# rpi-zero-psu.net
KiCad netlist of a schematic drawn in EAGLE
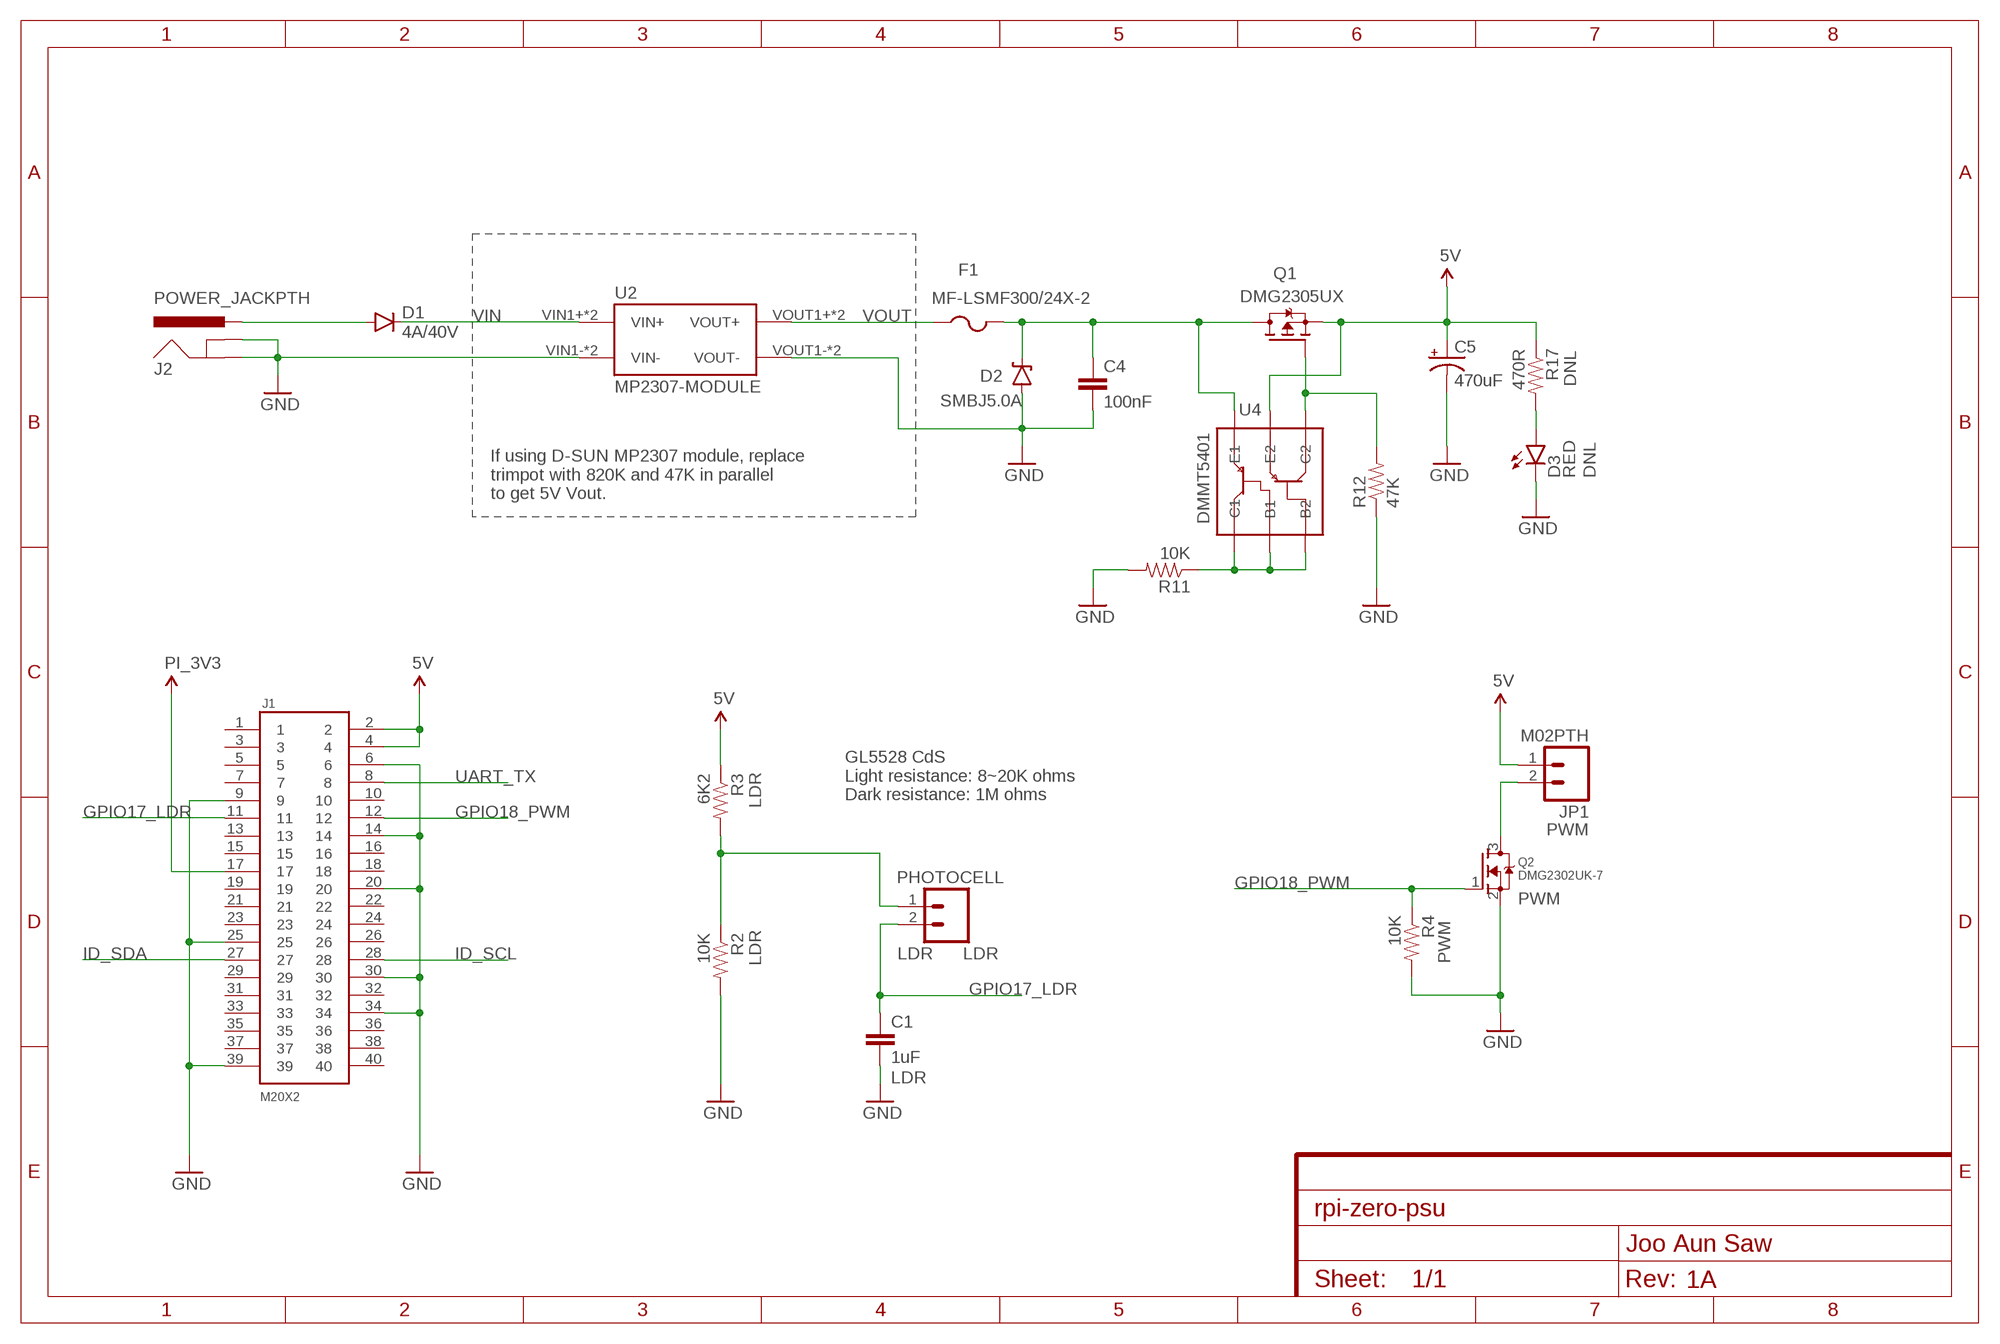
[diagram p0: schematic, sheet 1]

(export (version "E")
  (design (tool "Eeschema 10.0.6"))
  (components
    (comp (ref "C1")
      (value "1uF")
      (footprint "eagle-import:0805")
      (fields (field (name "PARTNO") "CC0805KKX7R8BB105"))
      (libsource (lib "eagle-import") (part "CAP0805"))
    )
    (comp (ref "C4")
      (value "100nF")
      (footprint "eagle-import:0805")
      (fields (field (name "PARTNO") "08055C104KAT2A"))
      (libsource (lib "eagle-import") (part "CAP0805"))
    )
    (comp (ref "C5")
      (value "470uF")
      (footprint "eagle-import:PANASONIC_F")
      (fields (field (name "ALT_PARTNO") "EEE-1CA471UP") (field (name "PARTNO") "875115150005"))
      (libsource (lib "eagle-import") (part "CAP_POLF"))
    )
    (comp (ref "D1")
      (value "4A/40V")
      (footprint "eagle-import:SMC")
      (fields (field (name "PARTNO") "MBRS340T3G"))
      (libsource (lib "eagle-import") (part "DIODEES3J"))
    )
    (comp (ref "D2")
      (value "SMBJ5.0A")
      (footprint "eagle-import:SMB-DIODE")
      (libsource (lib "eagle-import") (part "DIODE-ZENERSMB"))
    )
    (comp (ref "D3")
      (value "RED")
      (footprint "eagle-import:LED-1206")
      (fields (field (name "PARTNO") "LTST-C150CKT"))
      (libsource (lib "eagle-import") (part "LED-RED1206"))
    )
    (comp (ref "F1")
      (value "MF-LSMF300/24X-2")
      (footprint "eagle-import:2920")
      (libsource (lib "eagle-import") (part "PTCFUSE-2920"))
    )
    (comp (ref "J1")
      (value "M20X2")
      (footprint "eagle-import:2X20")
      (fields (field (name "PARTNO") "PPPC202LFBN-RC"))
      (libsource (lib "eagle-import") (part "M20X2"))
    )
    (comp (ref "J2")
      (value "POWER_JACKPTH")
      (footprint "eagle-import:POWER_JACK_PTH")
      (fields (field (name "PARTNO") "PJ-002A"))
      (libsource (lib "eagle-import") (part "POWER_JACKPTH"))
    )
    (comp (ref "JP1")
      (value "M02PTH")
      (footprint "eagle-import:1X02")
      (fields (field (name "PARTNO") "826936-2"))
      (libsource (lib "eagle-import") (part "M02PTH"))
    )
    (comp (ref "LDR")
      (value "PHOTOCELL")
      (footprint "eagle-import:1X02_NO_SILK")
      (libsource (lib "eagle-import") (part "M021X02_NO_SILK"))
    )
    (comp (ref "Q1")
      (value "DMG2305UX")
      (footprint "eagle-import:SOT-23")
      (fields (field (name "PARTNO") "DMG2305UX-7"))
      (libsource (lib "eagle-import") (part "MOSFET-P"))
    )
    (comp (ref "Q2")
      (value "DMG2302UK-7")
      (footprint "eagle-import:SOT23")
      (libsource (lib "eagle-import") (part "MOSFET-NREFLOW"))
    )
    (comp (ref "R2")
      (value "10K")
      (footprint "eagle-import:0805")
      (fields (field (name "PARTNO") "RC0805JR-0710KL"))
      (libsource (lib "eagle-import") (part "RESISTOR0805-RES"))
    )
    (comp (ref "R3")
      (value "6K2")
      (footprint "eagle-import:0805")
      (fields (field (name "PARTNO") "RC0805JR-076K2L"))
      (libsource (lib "eagle-import") (part "RESISTOR0805-RES"))
    )
    (comp (ref "R4")
      (value "10K")
      (footprint "eagle-import:0805")
      (fields (field (name "PARTNO") "RC0805JR-0710KL"))
      (libsource (lib "eagle-import") (part "RESISTOR0805-RES"))
    )
    (comp (ref "R11")
      (value "10K")
      (footprint "eagle-import:0805")
      (fields (field (name "PARTNO") "RC0805JR-0710KL"))
      (libsource (lib "eagle-import") (part "RESISTOR0805-RES"))
    )
    (comp (ref "R12")
      (value "47K")
      (footprint "eagle-import:0805")
      (fields (field (name "PARTNO") "RC0805FR-0747KL"))
      (libsource (lib "eagle-import") (part "RESISTOR0805-RES"))
    )
    (comp (ref "R17")
      (value "470R")
      (footprint "eagle-import:0805")
      (fields (field (name "PARTNO") "RC0805JR-07470RL"))
      (libsource (lib "eagle-import") (part "RESISTOR0805-RES"))
    )
    (comp (ref "U2")
      (value "MP2307-MODULE")
      (footprint "eagle-import:MP1584EN-MODULE")
      (fields (field (name "ALT_PARTNO") "IM130731001") (field (name "PARTNO") "106990005"))
      (libsource (lib "eagle-import") (part "DC-DC-MODULEMP2307-MODULE"))
    )
    (comp (ref "U4")
      (value "DMMT5401")
      (footprint "eagle-import:SOT23-6")
      (fields (field (name "PARTNO") "DMMT5401-7-F"))
      (libsource (lib "eagle-import") (part "DMMT5401SOT"))
    )
  )
  (nets
    (net (code "1") (name "/GPIO17_LDR") (class "Default")
      (node (ref "C1") (pin "1") (pinfunction "1_1") (pintype "passive"))
      (node (ref "J1") (pin "11") (pinfunction "11_11") (pintype "bidirectional"))
      (node (ref "LDR") (pin "2") (pinfunction "2_2") (pintype "passive"))
    )
    (net (code "2") (name "/GPIO18_PWM") (class "Default")
      (node (ref "J1") (pin "12") (pinfunction "12_12") (pintype "bidirectional"))
      (node (ref "Q2") (pin "1") (pinfunction "G_1") (pintype "bidirectional"))
      (node (ref "R4") (pin "1") (pinfunction "1_1") (pintype "passive"))
    )
    (net (code "3") (name "/ID_SCL") (class "Default")
      (node (ref "J1") (pin "28") (pinfunction "28_28") (pintype "bidirectional"))
    )
    (net (code "4") (name "/ID_SDA") (class "Default")
      (node (ref "J1") (pin "27") (pinfunction "27_27") (pintype "bidirectional"))
    )
    (net (code "5") (name "/UART_TX") (class "Default")
      (node (ref "J1") (pin "8") (pinfunction "8_8") (pintype "bidirectional"))
    )
    (net (code "6") (name "/VIN") (class "Default")
      (node (ref "D1") (pin "C") (pinfunction "C_C") (pintype "passive"))
      (node (ref "U2") (pin "VIN1+") (pinfunction "VIN+_VIN1+") (pintype "bidirectional"))
      (node (ref "U2") (pin "VIN2+") (pinfunction "VIN+_VIN2+") (pintype "bidirectional"))
    )
    (net (code "7") (name "/VOUT") (class "Default")
      (node (ref "F1") (pin "1") (pinfunction "1_1") (pintype "passive"))
      (node (ref "U2") (pin "VOUT1+") (pinfunction "VOUT+_VOUT1+") (pintype "bidirectional"))
      (node (ref "U2") (pin "VOUT2+") (pinfunction "VOUT+_VOUT2+") (pintype "bidirectional"))
    )
    (net (code "8") (name "5V") (class "Default")
      (node (ref "C5") (pin "+") (pinfunction "+_+") (pintype "passive"))
      (node (ref "J1") (pin "2") (pinfunction "2_2") (pintype "bidirectional"))
      (node (ref "J1") (pin "4") (pinfunction "4_4") (pintype "bidirectional"))
      (node (ref "JP1") (pin "1") (pinfunction "1_1") (pintype "passive"))
      (node (ref "Q1") (pin "2") (pinfunction "S_2") (pintype "passive"))
      (node (ref "R17") (pin "1") (pinfunction "1_1") (pintype "passive"))
      (node (ref "R3") (pin "1") (pinfunction "1_1") (pintype "passive"))
      (node (ref "U4") (pin "5") (pinfunction "E2_5") (pintype "bidirectional"))
    )
    (net (code "9") (name "GND") (class "Default")
      (node (ref "C1") (pin "2") (pinfunction "2_2") (pintype "passive"))
      (node (ref "C4") (pin "2") (pinfunction "2_2") (pintype "passive"))
      (node (ref "C5") (pin "-") (pinfunction "-_-") (pintype "passive"))
      (node (ref "D2") (pin "A") (pinfunction "A_A") (pintype "passive"))
      (node (ref "D3") (pin "C") (pinfunction "C_C") (pintype "passive"))
      (node (ref "J1") (pin "14") (pinfunction "14_14") (pintype "bidirectional"))
      (node (ref "J1") (pin "20") (pinfunction "20_20") (pintype "bidirectional"))
      (node (ref "J1") (pin "25") (pinfunction "25_25") (pintype "bidirectional"))
      (node (ref "J1") (pin "30") (pinfunction "30_30") (pintype "bidirectional"))
      (node (ref "J1") (pin "34") (pinfunction "34_34") (pintype "bidirectional"))
      (node (ref "J1") (pin "39") (pinfunction "39_39") (pintype "bidirectional"))
      (node (ref "J1") (pin "6") (pinfunction "6_6") (pintype "bidirectional"))
      (node (ref "J1") (pin "9") (pinfunction "9_9") (pintype "bidirectional"))
      (node (ref "J2") (pin "GND") (pinfunction "GND_GND") (pintype "bidirectional"))
      (node (ref "J2") (pin "GNDBREAK") (pinfunction "GNDBREAK_GNDBREAK") (pintype "bidirectional"))
      (node (ref "Q2") (pin "2") (pinfunction "S_2") (pintype "bidirectional"))
      (node (ref "R11") (pin "2") (pinfunction "2_2") (pintype "passive"))
      (node (ref "R12") (pin "1") (pinfunction "1_1") (pintype "passive"))
      (node (ref "R2") (pin "2") (pinfunction "2_2") (pintype "passive"))
      (node (ref "R4") (pin "2") (pinfunction "2_2") (pintype "passive"))
      (node (ref "U2") (pin "VIN1-") (pinfunction "VIN-_VIN1-") (pintype "bidirectional"))
      (node (ref "U2") (pin "VIN2-") (pinfunction "VIN-_VIN2-") (pintype "bidirectional"))
      (node (ref "U2") (pin "VOUT1-") (pinfunction "VOUT-_VOUT1-") (pintype "bidirectional"))
      (node (ref "U2") (pin "VOUT2-") (pinfunction "VOUT-_VOUT2-") (pintype "bidirectional"))
    )
    (net (code "10") (name "Net-(D1-PadA)") (class "Default")
      (node (ref "D1") (pin "A") (pinfunction "A_A") (pintype "passive"))
      (node (ref "J2") (pin "PWR") (pinfunction "PWR_PWR") (pintype "bidirectional"))
    )
    (net (code "11") (name "Net-(D3-PadA)") (class "Default")
      (node (ref "D3") (pin "A") (pinfunction "A_A") (pintype "passive"))
      (node (ref "R17") (pin "2") (pinfunction "2_2") (pintype "passive"))
    )
    (net (code "12") (name "Net-(LDR-Pad1)") (class "Default")
      (node (ref "LDR") (pin "1") (pinfunction "1_1") (pintype "passive"))
      (node (ref "R2") (pin "1") (pinfunction "1_1") (pintype "passive"))
      (node (ref "R3") (pin "2") (pinfunction "2_2") (pintype "passive"))
    )
    (net (code "13") (name "Net-(Q1-D)") (class "Default")
      (node (ref "C4") (pin "1") (pinfunction "1_1") (pintype "passive"))
      (node (ref "D2") (pin "C") (pinfunction "C_C") (pintype "passive"))
      (node (ref "F1") (pin "2") (pinfunction "2_2") (pintype "passive"))
      (node (ref "Q1") (pin "3") (pinfunction "D_3") (pintype "passive"))
      (node (ref "U4") (pin "6") (pinfunction "E1_6") (pintype "bidirectional"))
    )
    (net (code "14") (name "Net-(Q1-G)") (class "Default")
      (node (ref "Q1") (pin "1") (pinfunction "G_1") (pintype "passive"))
      (node (ref "R12") (pin "2") (pinfunction "2_2") (pintype "passive"))
      (node (ref "U4") (pin "4") (pinfunction "C2_4") (pintype "bidirectional"))
    )
    (net (code "15") (name "Net-(Q2-D)") (class "Default")
      (node (ref "JP1") (pin "2") (pinfunction "2_2") (pintype "passive"))
      (node (ref "Q2") (pin "3") (pinfunction "D_3") (pintype "bidirectional"))
    )
    (net (code "16") (name "Net-(U4-B1)") (class "Default")
      (node (ref "R11") (pin "1") (pinfunction "1_1") (pintype "passive"))
      (node (ref "U4") (pin "1") (pinfunction "C1_1") (pintype "bidirectional"))
      (node (ref "U4") (pin "2") (pinfunction "B1_2") (pintype "bidirectional"))
      (node (ref "U4") (pin "3") (pinfunction "B2_3") (pintype "bidirectional"))
    )
    (net (code "17") (name "PI_3V3") (class "Default")
      (node (ref "J1") (pin "17") (pinfunction "17_17") (pintype "bidirectional"))
    )
    (net (code "18") (name "unconnected-(J1-Pad1)") (class "Default")
      (node (ref "J1") (pin "1") (pinfunction "1_1") (pintype "bidirectional"))
    )
    (net (code "19") (name "unconnected-(J1-Pad3)") (class "Default")
      (node (ref "J1") (pin "3") (pinfunction "3_3") (pintype "bidirectional"))
    )
    (net (code "20") (name "unconnected-(J1-Pad5)") (class "Default")
      (node (ref "J1") (pin "5") (pinfunction "5_5") (pintype "bidirectional"))
    )
    (net (code "21") (name "unconnected-(J1-Pad7)") (class "Default")
      (node (ref "J1") (pin "7") (pinfunction "7_7") (pintype "bidirectional"))
    )
    (net (code "22") (name "unconnected-(J1-Pad10)") (class "Default")
      (node (ref "J1") (pin "10") (pinfunction "10_10") (pintype "bidirectional"))
    )
    (net (code "23") (name "unconnected-(J1-Pad13)") (class "Default")
      (node (ref "J1") (pin "13") (pinfunction "13_13") (pintype "bidirectional"))
    )
    (net (code "24") (name "unconnected-(J1-Pad15)") (class "Default")
      (node (ref "J1") (pin "15") (pinfunction "15_15") (pintype "bidirectional"))
    )
    (net (code "25") (name "unconnected-(J1-Pad16)") (class "Default")
      (node (ref "J1") (pin "16") (pinfunction "16_16") (pintype "bidirectional"))
    )
    (net (code "26") (name "unconnected-(J1-Pad18)") (class "Default")
      (node (ref "J1") (pin "18") (pinfunction "18_18") (pintype "bidirectional"))
    )
    (net (code "27") (name "unconnected-(J1-Pad19)") (class "Default")
      (node (ref "J1") (pin "19") (pinfunction "19_19") (pintype "bidirectional"))
    )
    (net (code "28") (name "unconnected-(J1-Pad21)") (class "Default")
      (node (ref "J1") (pin "21") (pinfunction "21_21") (pintype "bidirectional"))
    )
    (net (code "29") (name "unconnected-(J1-Pad22)") (class "Default")
      (node (ref "J1") (pin "22") (pinfunction "22_22") (pintype "bidirectional"))
    )
    (net (code "30") (name "unconnected-(J1-Pad23)") (class "Default")
      (node (ref "J1") (pin "23") (pinfunction "23_23") (pintype "bidirectional"))
    )
    (net (code "31") (name "unconnected-(J1-Pad24)") (class "Default")
      (node (ref "J1") (pin "24") (pinfunction "24_24") (pintype "bidirectional"))
    )
    (net (code "32") (name "unconnected-(J1-Pad26)") (class "Default")
      (node (ref "J1") (pin "26") (pinfunction "26_26") (pintype "bidirectional"))
    )
    (net (code "33") (name "unconnected-(J1-Pad29)") (class "Default")
      (node (ref "J1") (pin "29") (pinfunction "29_29") (pintype "bidirectional"))
    )
    (net (code "34") (name "unconnected-(J1-Pad31)") (class "Default")
      (node (ref "J1") (pin "31") (pinfunction "31_31") (pintype "bidirectional"))
    )
    (net (code "35") (name "unconnected-(J1-Pad32)") (class "Default")
      (node (ref "J1") (pin "32") (pinfunction "32_32") (pintype "bidirectional"))
    )
    (net (code "36") (name "unconnected-(J1-Pad33)") (class "Default")
      (node (ref "J1") (pin "33") (pinfunction "33_33") (pintype "bidirectional"))
    )
    (net (code "37") (name "unconnected-(J1-Pad35)") (class "Default")
      (node (ref "J1") (pin "35") (pinfunction "35_35") (pintype "bidirectional"))
    )
    (net (code "38") (name "unconnected-(J1-Pad36)") (class "Default")
      (node (ref "J1") (pin "36") (pinfunction "36_36") (pintype "bidirectional"))
    )
    (net (code "39") (name "unconnected-(J1-Pad37)") (class "Default")
      (node (ref "J1") (pin "37") (pinfunction "37_37") (pintype "bidirectional"))
    )
    (net (code "40") (name "unconnected-(J1-Pad38)") (class "Default")
      (node (ref "J1") (pin "38") (pinfunction "38_38") (pintype "bidirectional"))
    )
    (net (code "41") (name "unconnected-(J1-Pad40)") (class "Default")
      (node (ref "J1") (pin "40") (pinfunction "40_40") (pintype "bidirectional"))
    )
  )
)
